# DP.net
KiCad netlist of a schematic drawn in Altium Designer
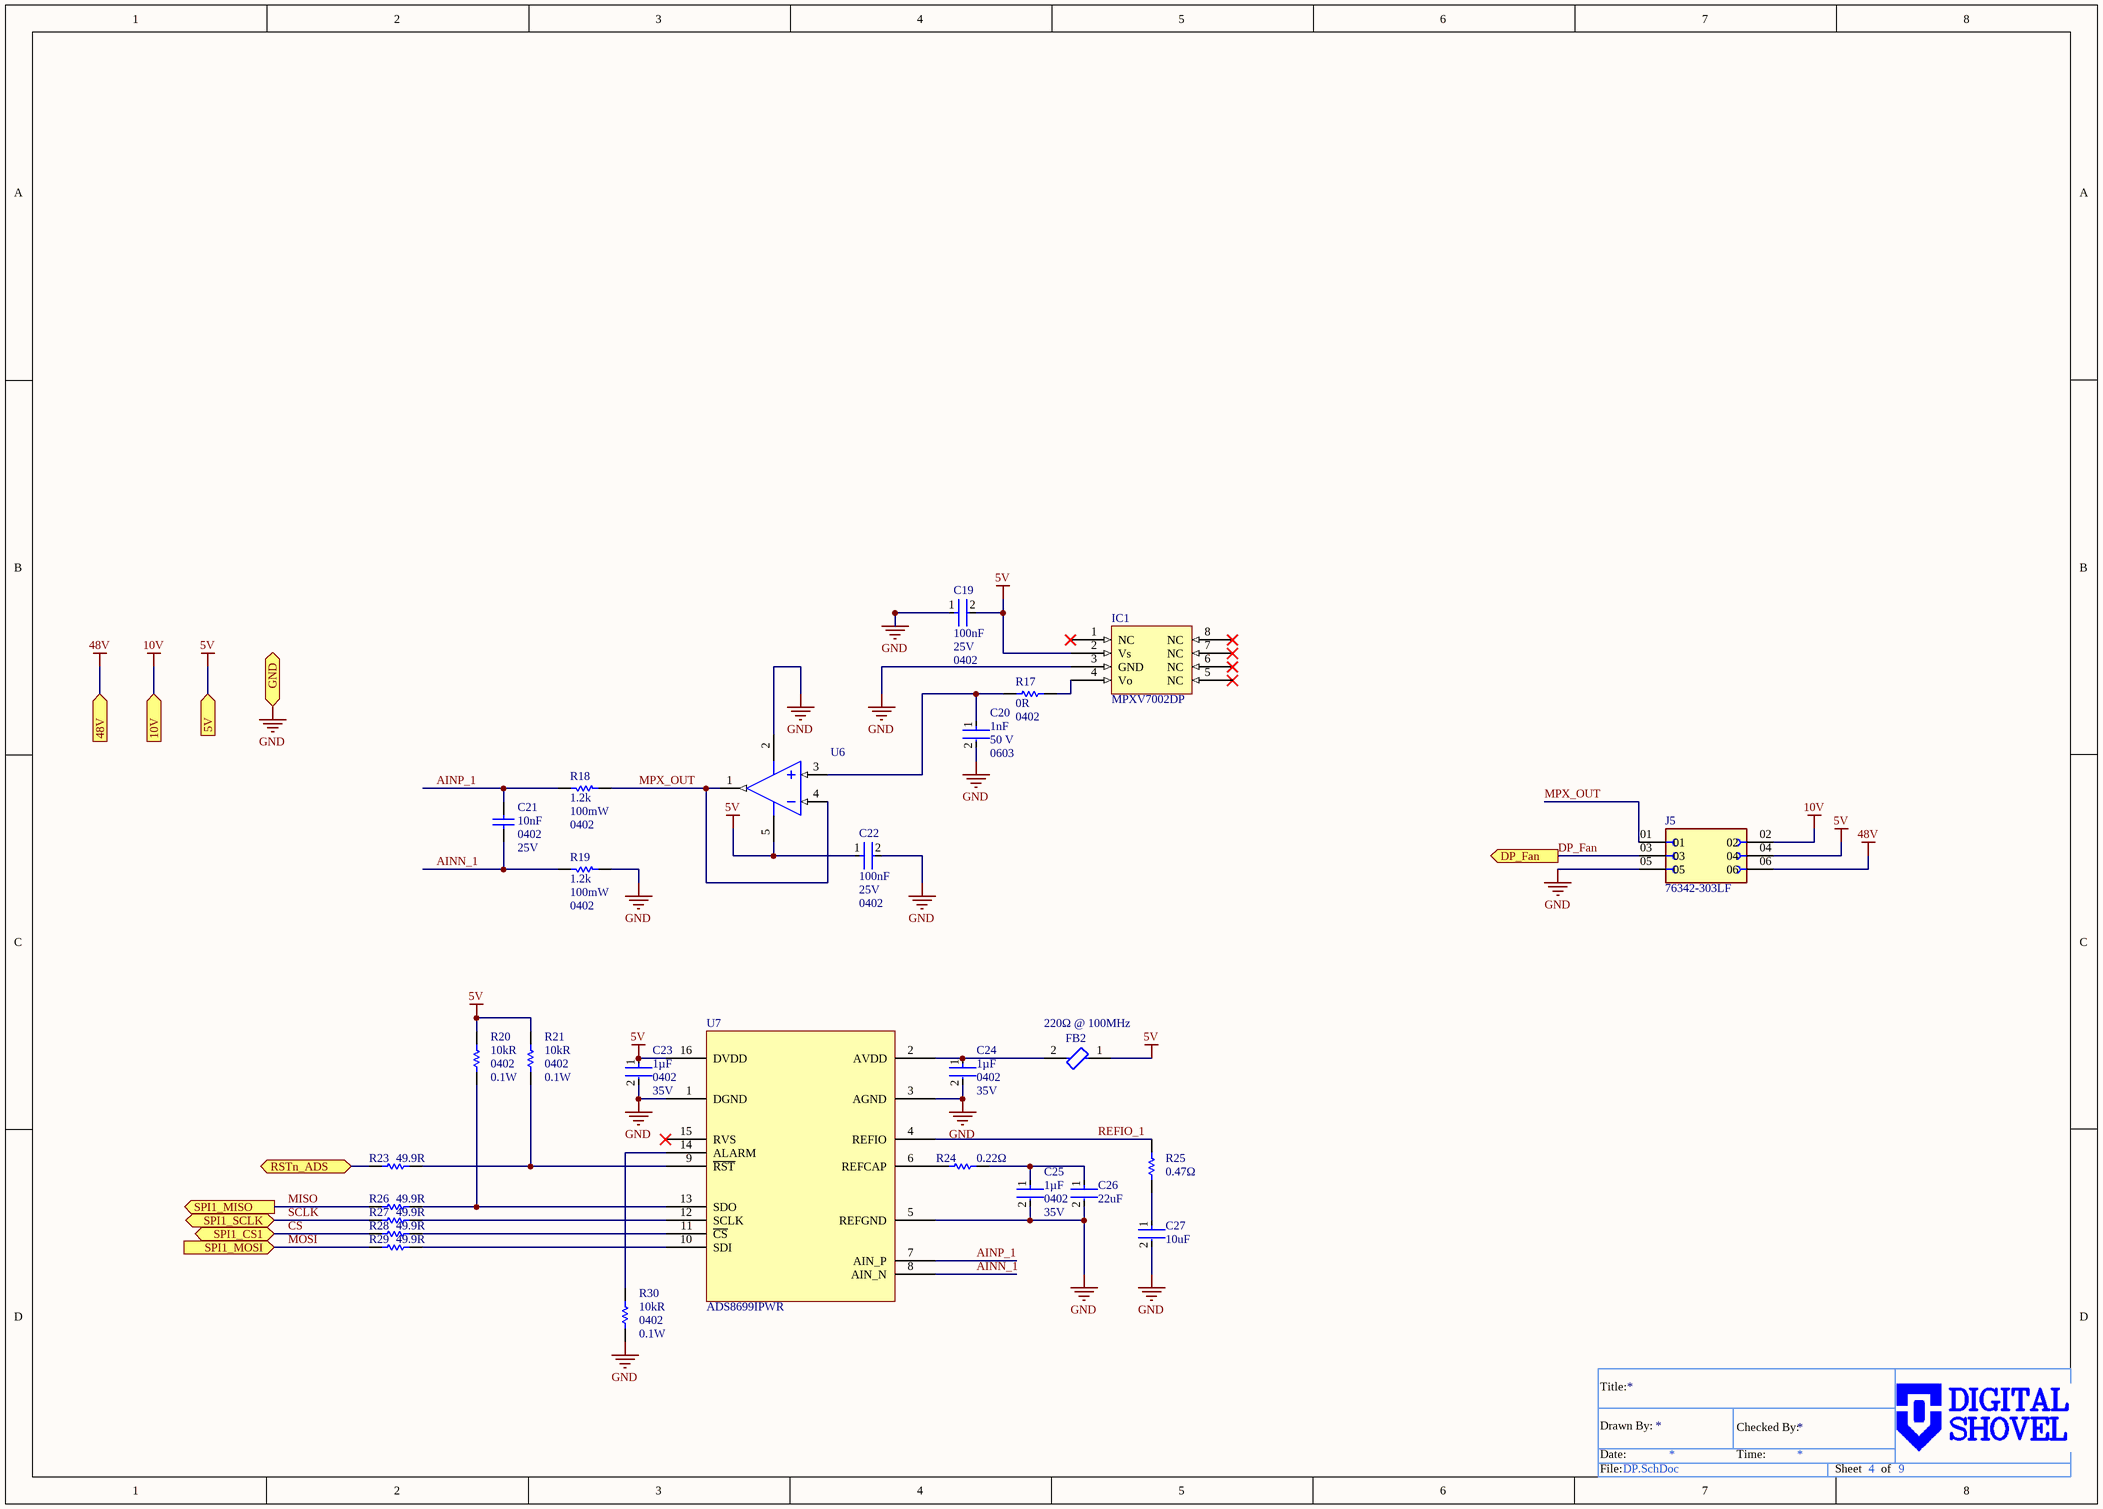
[diagram p0: DP.SchDoc]

(export (version "E")
  (design (tool "Eeschema 10.0.6"))
  (components
    (comp (ref "C19")
      (value "100nF")
      (footprint "FP-CL830-IPC_A")
      (fields
        (field (name "VOLTAGE RATING") "25V")
        (field (name "CASE/PACKAGE") "0402")
        (field (name "Comment") "CL05B104KA5NNNC")
      )
      (libsource (lib "Digital Shovel") (part "b4654b650e69147ec39a6b967a45e02"))
    )
    (comp (ref "C20")
      (value "1nF")
      (footprint "FP-C0603C-CF-MFG")
      (description "CAP CER 1000PF 50V X7R 0603")
      (fields
        (field (name "TOLERANCE") "0.1")
        (field (name "MANUFACTURER PART NUMBER") "C0603C102K5RACTU")
        (field (name "VOLTAGE RATING") "50 V")
        (field (name "PACKAGE") "0603")
      )
      (libsource (lib "Altium Content Vault") (part "b4654b650e69147ec39a6b967a45e02"))
    )
    (comp (ref "C21")
      (value "10nF")
      (footprint "CAPC1005X55X25ML05T10")
      (fields
        (field (name "MANUFACTURER") "Murata")
        (field (name "PACKAGE") "0402")
        (field (name "PARAMETER 1") "25V")
        (field (name "Comment") "GRM155R71E103KA01D")
      )
      (libsource (lib "Digital Shovel") (part "CAP"))
    )
    (comp (ref "C22")
      (value "100nF")
      (footprint "FP-CL830-IPC_A")
      (fields
        (field (name "VOLTAGE RATING") "25V")
        (field (name "CASE/PACKAGE") "0402")
        (field (name "Comment") "CL05B104KA5NNNC")
      )
      (libsource (lib "Digital Shovel") (part "b4654b650e69147ec39a6b967a45e02"))
    )
    (comp (ref "C23")
      (value "1µF")
      (footprint "FP-C1005-050-0_05-IPC_A")
      (fields
        (field (name "CASE/PACKAGE") "0402")
        (field (name "VOLTAGE RATING") "35V")
        (field (name "Comment") "C1005JB1V105K050BC")
      )
      (libsource (lib "Digital Shovel") (part "b4654b650e69147ec39a6b967a45e02"))
    )
    (comp (ref "C24")
      (value "1µF")
      (footprint "FP-C1005-050-0_05-IPC_A")
      (fields
        (field (name "CASE/PACKAGE") "0402")
        (field (name "VOLTAGE RATING") "35V")
        (field (name "Comment") "C1005JB1V105K050BC")
      )
      (libsource (lib "Digital Shovel") (part "b4654b650e69147ec39a6b967a45e02"))
    )
    (comp (ref "C25")
      (value "1µF")
      (footprint "FP-C1005-050-0_05-IPC_A")
      (fields
        (field (name "CASE/PACKAGE") "0402")
        (field (name "VOLTAGE RATING") "35V")
        (field (name "Comment") "C1005JB1V105K050BC")
      )
      (libsource (lib "Digital Shovel") (part "b4654b650e69147ec39a6b967a45e02"))
    )
    (comp (ref "C26")
      (value "22uF")
      (footprint "FP-GRM21B-0_2-e0_2_0_7-IPC_A")
      (description "Chip Multilayer Ceramic Capacitors for General Purpose, 0805, 22uF, X5R, 15%, 20%, 16V")
      (fields (field (name "TOLERANCE") "20%") (field (name "Comment") "GRM21BR61C226ME44L"))
      (libsource (lib "Altium Content Vault") (part "b4654b650e69147ec39a6b967a45e02"))
    )
    (comp (ref "C27")
      (value "10uF")
      (footprint "FP-CL21-IPC_B")
      (description "CL21 Series 0805 10uF 25V ±10% Tolerance X5R Multilayer Ceramic Chip Capacitor")
      (fields (field (name "TOLERANCE") "10%") (field (name "Comment") "CL21A106KAFN3NE"))
      (libsource (lib "Altium Content Vault") (part "b4654b650e69147ec39a6b967a45e02"))
    )
    (comp (ref "FB2")
      (value "220Ω @ 100MHz")
      (footprint "FP-BLM18-0_15-t0_8-IPC_C")
      (description "Ferrite Chip, 1 Function(s), 2.2A, 2 Pin(s)")
      (fields (field (name "Comment") "BLM18KG221SN1D"))
      (libsource (lib "Digital Shovel") (part "5f30dd21d616792df468990f7003faa"))
    )
    (comp (ref "IC1")
      (value "MPXV7002DP")
      (footprint "MPXV7002DP-Footprint-1")
      (fields (field (name "MANUFACTURER") "NXP"))
      (libsource (lib "Digital Shovel") (part "MPXV7002DP-Symbol-1"))
    )
    (comp (ref "J5")
      (value "76342-303LF")
      (footprint "AMPHENOL_76342-303LF")
      (fields (field (name "MF") "Amphenol"))
      (libsource (lib "Digital Shovel") (part "76342-303LF"))
    )
    (comp (ref "R17")
      (value "0R")
      (footprint "FP-RK73Z1E-IPC_B")
      (description "Metal Glaze/thick Film, 0ohm, Surface Mount, 0402")
      (fields (field (name "PACKAGE") "0402") (field (name "Comment") "RK73Z1ETTP"))
      (libsource (lib "Digital Shovel") (part "1029c3af85768c4190bb7ad29bc67b5"))
    )
    (comp (ref "R18")
      (value "1.2k")
      (footprint "RESC1005X40X25LL10T10")
      (fields
        (field (name "POWER") "100mW")
        (field (name "TOLERANCE") "1%")
        (field (name "CASE/PACKAGE") "0402")
        (field (name "Comment") "RK73H1ETTP1201F")
      )
      (libsource (lib "Digital Shovel") (part "RES"))
    )
    (comp (ref "R19")
      (value "1.2k")
      (footprint "RESC1005X40X25LL10T10")
      (fields
        (field (name "POWER") "100mW")
        (field (name "TOLERANCE") "1%")
        (field (name "CASE/PACKAGE") "0402")
        (field (name "Comment") "RK73H1ETTP1201F")
      )
      (libsource (lib "Digital Shovel") (part "RES"))
    )
    (comp (ref "R20")
      (value "10kR")
      (footprint "RESC1005X40X25LL10T10")
      (fields
        (field (name "PACKAGE") "0402")
        (field (name "POWER RATING") "0.1W")
        (field (name "Comment") "RK73H1ETTP1002F")
      )
      (libsource (lib "Digital Shovel") (part "RES"))
    )
    (comp (ref "R21")
      (value "10kR")
      (footprint "RESC1005X40X25LL10T10")
      (fields
        (field (name "PACKAGE") "0402")
        (field (name "POWER RATING") "0.1W")
        (field (name "Comment") "RK73H1ETTP1002F")
      )
      (libsource (lib "Digital Shovel") (part "RES"))
    )
    (comp (ref "R23")
      (value "49.9R")
      (footprint "RESC1005X40X25LL10T10")
      (fields (field (name "Comment") "RK73H1ETTP49R9F"))
      (libsource (lib "Digital Shovel") (part "RES"))
    )
    (comp (ref "R24")
      (value "0.22Ω")
      (footprint "RESC1608X55X30NL15T15")
      (fields (field (name "PART NUMBER") "ERJ-3RQFR22V") (field (name "MANUFACTURER") "Panasonic"))
      (libsource (lib "Altium Content Vault") (part "RES"))
    )
    (comp (ref "R25")
      (value "0.47Ω")
      (footprint "RESC1608X55X30ML15T15")
      (fields (field (name "MANUFACTURER") "Panasonic") (field (name "PART NUMBER") "ERJ-3RQFR47V"))
      (libsource (lib "Altium Content Vault") (part "RES"))
    )
    (comp (ref "R26")
      (value "49.9R")
      (footprint "RESC1005X40X25LL10T10")
      (fields (field (name "Comment") "RK73H1ETTP49R9F"))
      (libsource (lib "Digital Shovel") (part "RES"))
    )
    (comp (ref "R27")
      (value "49.9R")
      (footprint "RESC1005X40X25LL10T10")
      (fields (field (name "Comment") "RK73H1ETTP49R9F"))
      (libsource (lib "Digital Shovel") (part "RES"))
    )
    (comp (ref "R28")
      (value "49.9R")
      (footprint "RESC1005X40X25LL10T10")
      (fields (field (name "Comment") "RK73H1ETTP49R9F"))
      (libsource (lib "Digital Shovel") (part "RES"))
    )
    (comp (ref "R29")
      (value "49.9R")
      (footprint "RESC1005X40X25LL10T10")
      (fields (field (name "Comment") "RK73H1ETTP49R9F"))
      (libsource (lib "Digital Shovel") (part "RES"))
    )
    (comp (ref "R30")
      (value "10kR")
      (footprint "RESC1005X40X25LL10T10")
      (fields
        (field (name "PACKAGE") "0402")
        (field (name "POWER RATING") "0.1W")
        (field (name "Comment") "RK73H1ETTP1002F")
      )
      (libsource (lib "Digital Shovel") (part "RES"))
    )
    (comp (ref "U6")
      (value "THS4281DBVR")
      (footprint "DBV0005A_L")
      (fields (field (name "MANUFACTURER") "Texas Instruments"))
      (libsource (lib "Altium Content Vault") (part "TI-AMP-S3-2-DBV5"))
    )
    (comp (ref "U7")
      (value "ADS8699IPWR")
      (footprint "TSOP65P640X120-16N")
      (description "ADC, Successive Approximation, 18-Bit, 1 Func, 1 Channel, Serial Access, PDSO16")
      (libsource (lib "Digital Shovel") (part "ADS8699"))
    )
  )
  (nets
    (net (code "1") (name "/AINN_1") (class "Default")
      (node (ref "C21") (pin "1") (pinfunction "1_1") (pintype "passive"))
      (node (ref "R19") (pin "2") (pinfunction "2_2") (pintype "passive"))
      (node (ref "U7") (pin "8") (pinfunction "AIN_N_8") (pintype "passive"))
    )
    (net (code "2") (name "/AINP_1") (class "Default")
      (node (ref "C21") (pin "2") (pinfunction "2_2") (pintype "passive"))
      (node (ref "R18") (pin "2") (pinfunction "2_2") (pintype "passive"))
      (node (ref "U7") (pin "7") (pinfunction "AIN_P_7") (pintype "passive"))
    )
    (net (code "3") (name "/DP_Fan") (class "Default")
      (node (ref "J5") (pin "03") (pinfunction "03_03") (pintype "passive"))
    )
    (net (code "4") (name "/MISO") (class "Default")
      (node (ref "R26") (pin "1") (pinfunction "1_1") (pintype "passive"))
    )
    (net (code "5") (name "/MOSI") (class "Default")
      (node (ref "R29") (pin "1") (pinfunction "1_1") (pintype "passive"))
    )
    (net (code "6") (name "/MPX_OUT") (class "Default")
      (node (ref "J5") (pin "01") (pinfunction "01_01") (pintype "passive"))
      (node (ref "R18") (pin "1") (pinfunction "1_1") (pintype "passive"))
      (node (ref "U6") (pin "1") (pinfunction "VOUT_1") (pintype "output"))
      (node (ref "U6") (pin "4") (pinfunction "IN-_4") (pintype "input"))
    )
    (net (code "7") (name "/REFIO_1") (class "Default")
      (node (ref "R25") (pin "2") (pinfunction "2_2") (pintype "passive"))
      (node (ref "U7") (pin "4") (pinfunction "REFIO_4") (pintype "passive"))
    )
    (net (code "8") (name "/RSTn_ADS") (class "Default")
      (node (ref "R23") (pin "1") (pinfunction "1_1") (pintype "passive"))
    )
    (net (code "9") (name "/SCLK") (class "Default")
      (node (ref "R27") (pin "1") (pinfunction "1_1") (pintype "passive"))
    )
    (net (code "10") (name "/~{C}S") (class "Default")
      (node (ref "R28") (pin "1") (pinfunction "1_1") (pintype "passive"))
    )
    (net (code "11") (name "5V") (class "Default")
      (node (ref "C19") (pin "2") (pinfunction "2_2") (pintype "passive"))
      (node (ref "C22") (pin "1") (pinfunction "1_1") (pintype "passive"))
      (node (ref "C23") (pin "1") (pinfunction "1_1") (pintype "passive"))
      (node (ref "FB2") (pin "1") (pinfunction "1_1") (pintype "passive"))
      (node (ref "IC1") (pin "2") (pinfunction "Vs_2") (pintype "input"))
      (node (ref "J5") (pin "04") (pinfunction "04_04") (pintype "passive"))
      (node (ref "R20") (pin "2") (pinfunction "2_2") (pintype "passive"))
      (node (ref "R21") (pin "2") (pinfunction "2_2") (pintype "passive"))
      (node (ref "U6") (pin "5") (pinfunction "VS+_5") (pintype "power_in"))
      (node (ref "U7") (pin "16") (pinfunction "DVDD_16") (pintype "passive"))
    )
    (net (code "12") (name "10V") (class "Default")
      (node (ref "J5") (pin "02") (pinfunction "02_02") (pintype "passive"))
    )
    (net (code "13") (name "48V") (class "Default")
      (node (ref "J5") (pin "06") (pinfunction "06_06") (pintype "passive"))
    )
    (net (code "14") (name "GND") (class "Default")
      (node (ref "C19") (pin "1") (pinfunction "1_1") (pintype "passive"))
      (node (ref "C20") (pin "2") (pinfunction "2_2") (pintype "passive"))
      (node (ref "C22") (pin "2") (pinfunction "2_2") (pintype "passive"))
      (node (ref "C23") (pin "2") (pinfunction "2_2") (pintype "passive"))
      (node (ref "C24") (pin "2") (pinfunction "2_2") (pintype "passive"))
      (node (ref "C25") (pin "2") (pinfunction "2_2") (pintype "passive"))
      (node (ref "C26") (pin "2") (pinfunction "2_2") (pintype "passive"))
      (node (ref "C27") (pin "2") (pinfunction "2_2") (pintype "passive"))
      (node (ref "IC1") (pin "3") (pinfunction "GND_3") (pintype "input"))
      (node (ref "J5") (pin "05") (pinfunction "05_05") (pintype "passive"))
      (node (ref "R19") (pin "1") (pinfunction "1_1") (pintype "passive"))
      (node (ref "R30") (pin "1") (pinfunction "1_1") (pintype "passive"))
      (node (ref "U6") (pin "2") (pinfunction "VS-_2") (pintype "power_in"))
      (node (ref "U7") (pin "1") (pinfunction "DGND_1") (pintype "passive"))
      (node (ref "U7") (pin "3") (pinfunction "AGND_3") (pintype "passive"))
      (node (ref "U7") (pin "5") (pinfunction "REFGND_5") (pintype "passive"))
    )
    (net (code "15") (name "Net-(C25-Pad1)") (class "Default")
      (node (ref "C25") (pin "1") (pinfunction "1_1") (pintype "passive"))
      (node (ref "C26") (pin "1") (pinfunction "1_1") (pintype "passive"))
      (node (ref "R24") (pin "2") (pinfunction "2_2") (pintype "passive"))
    )
    (net (code "16") (name "Net-(C27-Pad1)") (class "Default")
      (node (ref "C27") (pin "1") (pinfunction "1_1") (pintype "passive"))
      (node (ref "R25") (pin "1") (pinfunction "1_1") (pintype "passive"))
    )
    (net (code "17") (name "Net-(IC1-Vo)") (class "Default")
      (node (ref "IC1") (pin "4") (pinfunction "Vo_4") (pintype "input"))
      (node (ref "R17") (pin "1") (pinfunction "1_1") (pintype "passive"))
    )
    (net (code "18") (name "Net-(U6-IN+)") (class "Default")
      (node (ref "C20") (pin "1") (pinfunction "1_1") (pintype "passive"))
      (node (ref "R17") (pin "2") (pinfunction "2_2") (pintype "passive"))
      (node (ref "U6") (pin "3") (pinfunction "IN+_3") (pintype "input"))
    )
    (net (code "19") (name "Net-(U7-ALARM)") (class "Default")
      (node (ref "R30") (pin "2") (pinfunction "2_2") (pintype "passive"))
      (node (ref "U7") (pin "14") (pinfunction "ALARM_14") (pintype "passive"))
    )
    (net (code "20") (name "Net-(U7-AVDD)") (class "Default")
      (node (ref "C24") (pin "1") (pinfunction "1_1") (pintype "passive"))
      (node (ref "FB2") (pin "2") (pinfunction "2_2") (pintype "passive"))
      (node (ref "U7") (pin "2") (pinfunction "AVDD_2") (pintype "passive"))
    )
    (net (code "21") (name "Net-(U7-REFCAP)") (class "Default")
      (node (ref "R24") (pin "1") (pinfunction "1_1") (pintype "passive"))
      (node (ref "U7") (pin "6") (pinfunction "REFCAP_6") (pintype "passive"))
    )
    (net (code "22") (name "Net-(U7-SCLK)") (class "Default")
      (node (ref "R27") (pin "2") (pinfunction "2_2") (pintype "passive"))
      (node (ref "U7") (pin "12") (pinfunction "SCLK_12") (pintype "passive"))
    )
    (net (code "23") (name "Net-(U7-SDI)") (class "Default")
      (node (ref "R29") (pin "2") (pinfunction "2_2") (pintype "passive"))
      (node (ref "U7") (pin "10") (pinfunction "SDI_10") (pintype "passive"))
    )
    (net (code "24") (name "Net-(U7-SDO)") (class "Default")
      (node (ref "R20") (pin "1") (pinfunction "1_1") (pintype "passive"))
      (node (ref "R26") (pin "2") (pinfunction "2_2") (pintype "passive"))
      (node (ref "U7") (pin "13") (pinfunction "SDO_13") (pintype "passive"))
    )
    (net (code "25") (name "Net-(U7-~{CS})") (class "Default")
      (node (ref "R28") (pin "2") (pinfunction "2_2") (pintype "passive"))
      (node (ref "U7") (pin "11") (pinfunction "~{CS}_11") (pintype "passive"))
    )
    (net (code "26") (name "Net-(U7-~{RST})") (class "Default")
      (node (ref "R21") (pin "1") (pinfunction "1_1") (pintype "passive"))
      (node (ref "R23") (pin "2") (pinfunction "2_2") (pintype "passive"))
      (node (ref "U7") (pin "9") (pinfunction "~{RST}_9") (pintype "passive"))
    )
    (net (code "27") (name "unconnected-(IC1-NC-Pad1)") (class "Default")
      (node (ref "IC1") (pin "1") (pinfunction "NC_1") (pintype "input+no_connect"))
    )
    (net (code "28") (name "unconnected-(IC1-NC-Pad5)") (class "Default")
      (node (ref "IC1") (pin "5") (pinfunction "NC_5") (pintype "input+no_connect"))
    )
    (net (code "29") (name "unconnected-(IC1-NC-Pad6)") (class "Default")
      (node (ref "IC1") (pin "6") (pinfunction "NC_6") (pintype "input+no_connect"))
    )
    (net (code "30") (name "unconnected-(IC1-NC-Pad7)") (class "Default")
      (node (ref "IC1") (pin "7") (pinfunction "NC_7") (pintype "input+no_connect"))
    )
    (net (code "31") (name "unconnected-(IC1-NC-Pad8)") (class "Default")
      (node (ref "IC1") (pin "8") (pinfunction "NC_8") (pintype "input+no_connect"))
    )
    (net (code "32") (name "unconnected-(U7-RVS-Pad15)") (class "Default")
      (node (ref "U7") (pin "15") (pinfunction "RVS_15") (pintype "passive+no_connect"))
    )
  )
)
